# Optical_RX.net
KiCad netlist of a schematic drawn in Altium Designer
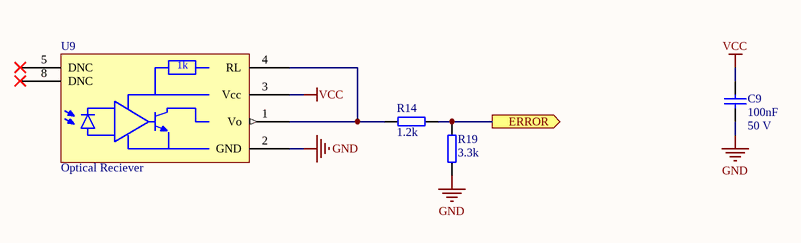
[diagram p0: Optical_RX.SchDoc]

(export (version "E")
  (design (tool "Eeschema 10.0.6"))
  (components
    (comp (ref "C9")
      (value "100nF")
      (footprint "C_0603(1608)100_L")
      (description "CAP 0603 (1608 Metric) SMD")
      (fields
        (field (name "TOLERANCE") "±20%")
        (field (name "MF") "Yageo")
        (field (name "VOLTAGE") "50 V")
        (field (name "CREATED") "2018_09_06_AGeiger")
      )
      (libsource (lib "UZOhm_Optical") (part "C_0603"))
    )
    (comp (ref "R14")
      (value "1.2k")
      (footprint "R_0603_N")
      (description "SMD Resistor 0603")
      (fields
        (field (name "TOLERANCE") "1%")
        (field (name "VOLTAGE") "75 V")
        (field (name "CREATED") "2018_09_06_AGeiger")
      )
      (libsource (lib "UZOhm_Optical") (part "R_0603"))
    )
    (comp (ref "R19")
      (value "3.3k")
      (footprint "R_0603_N")
      (description "SMD Resistor 0603")
      (fields
        (field (name "TOLERANCE") "1%")
        (field (name "VOLTAGE") "75 V")
        (field (name "CREATED") "2018_09_06_AGeiger")
      )
      (libsource (lib "UZOhm_Optical") (part "R_0603"))
    )
    (comp (ref "U9")
      (value "Optical Reciever")
      (footprint "HFBRx5XX")
      (description "Fibre Optic Transmitters, Receivers, Transceivers V-LINK HORIZ 5MBd RC VR RoHS")
      (fields
        (field (name "MF") "Boadcom/Avago")
        (field (name "MPN") "HFBR-2521Z")
        (field (name "CREATED") "2019_04_09_Kreppel")
      )
      (libsource (lib "UZOhm_Optical") (part "HFBR-2528Z"))
    )
  )
  (nets
    (net (code "1") (name "/ERROR") (class "Default")
      (node (ref "R14") (pin "2") (pinfunction "2_2") (pintype "passive"))
      (node (ref "R19") (pin "2") (pinfunction "2_2") (pintype "passive"))
    )
    (net (code "2") (name "GND") (class "Default")
      (node (ref "C9") (pin "2") (pinfunction "2_2") (pintype "passive"))
      (node (ref "R19") (pin "1") (pinfunction "1_1") (pintype "passive"))
      (node (ref "U9") (pin "2") (pinfunction "GND_2") (pintype "power_in"))
    )
    (net (code "3") (name "Net-(U9-RL)") (class "Default")
      (node (ref "R14") (pin "1") (pinfunction "1_1") (pintype "passive"))
      (node (ref "U9") (pin "1") (pinfunction "Vo_1") (pintype "output"))
      (node (ref "U9") (pin "4") (pinfunction "RL_4") (pintype "passive"))
    )
    (net (code "4") (name "VCC") (class "Default")
      (node (ref "C9") (pin "1") (pinfunction "1_1") (pintype "passive"))
      (node (ref "U9") (pin "3") (pinfunction "Vcc_3") (pintype "power_in"))
    )
    (net (code "5") (name "unconnected-(U9-DNC-Pad5)") (class "Default")
      (node (ref "U9") (pin "5") (pinfunction "DNC_5") (pintype "passive+no_connect"))
    )
    (net (code "6") (name "unconnected-(U9-DNC-Pad8)") (class "Default")
      (node (ref "U9") (pin "8") (pinfunction "DNC_8") (pintype "passive+no_connect"))
    )
  )
)
